# FDC1004Q.net
KiCad netlist of a schematic drawn in EAGLE
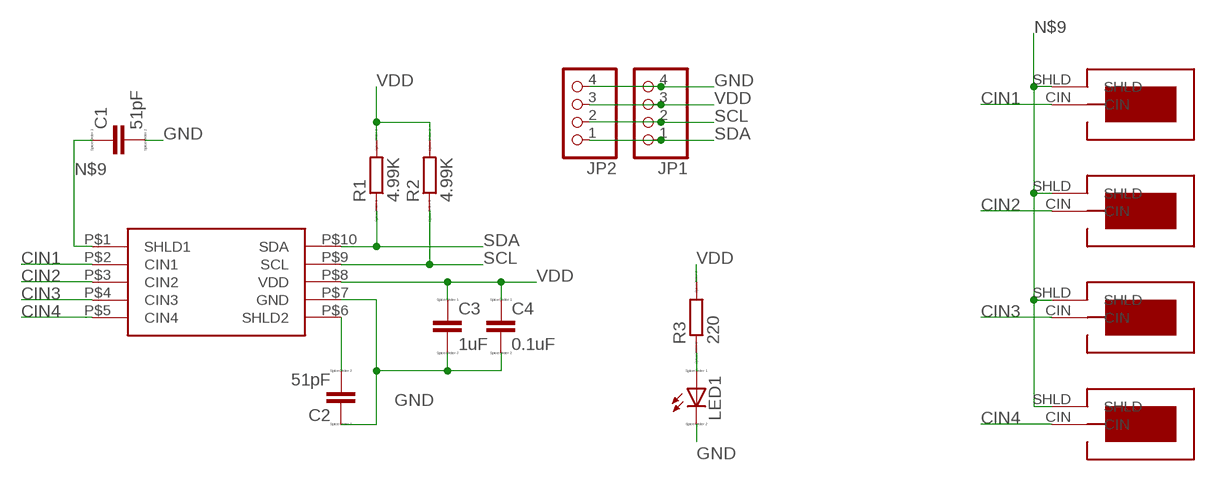
[diagram p0: schematic, sheet 1]

(export (version "E")
  (design (tool "Eeschema 10.0.6"))
  (components
    (comp (ref "C1")
      (value "51pF")
      (footprint "eagle-import:C0805")
      (libsource (lib "eagle-import") (part "C"))
    )
    (comp (ref "C2")
      (value "51pF")
      (footprint "eagle-import:C0805")
      (libsource (lib "eagle-import") (part "C"))
    )
    (comp (ref "C3")
      (value "1uF")
      (footprint "eagle-import:C0805")
      (libsource (lib "eagle-import") (part "C"))
    )
    (comp (ref "C4")
      (value "0.1uF")
      (footprint "eagle-import:C0805")
      (libsource (lib "eagle-import") (part "C"))
    )
    (comp (ref "JP1")
      (value "PINHD-1X4")
      (footprint "eagle-import:1X04")
      (libsource (lib "eagle-import") (part "PINHD-1X4"))
    )
    (comp (ref "JP2")
      (value "PINHD-1X4")
      (footprint "eagle-import:1X04")
      (libsource (lib "eagle-import") (part "PINHD-1X4"))
    )
    (comp (ref "LED1")
      (value "LED_ESML0603")
      (footprint "eagle-import:LED_SML0603")
      (libsource (lib "eagle-import") (part "LED_ESML0603"))
    )
    (comp (ref "R1")
      (value "4.99K")
      (footprint "eagle-import:R0805")
      (libsource (lib "eagle-import") (part "R"))
    )
    (comp (ref "R2")
      (value "4.99K")
      (footprint "eagle-import:R0805")
      (libsource (lib "eagle-import") (part "R"))
    )
    (comp (ref "R3")
      (value "220")
      (footprint "eagle-import:R0805")
      (libsource (lib "eagle-import") (part "R"))
    )
    (comp (ref "SENSOR1")
      (value "SENSOR")
      (footprint "eagle-import:SENSOR_1X1")
      (libsource (lib "eagle-import") (part "SENSOR"))
    )
    (comp (ref "SENSOR2")
      (value "SENSOR")
      (footprint "eagle-import:SENSOR_1X1")
      (libsource (lib "eagle-import") (part "SENSOR"))
    )
    (comp (ref "SENSOR3")
      (value "SENSOR")
      (footprint "eagle-import:SENSOR_1X1")
      (libsource (lib "eagle-import") (part "SENSOR"))
    )
    (comp (ref "SENSOR4")
      (value "SENSOR")
      (footprint "eagle-import:SENSOR_1X1")
      (libsource (lib "eagle-import") (part "SENSOR"))
    )
    (comp (ref "U$1")
      (value "FDC1004Q")
      (footprint "eagle-import:DGS")
      (libsource (lib "eagle-import") (part "FDC1004Q"))
    )
  )
  (nets
    (net (code "1") (name "/CIN1") (class "Default")
      (node (ref "SENSOR1") (pin "CIN") (pinfunction "CIN_CIN") (pintype "bidirectional"))
      (node (ref "U$1") (pin "P$2") (pinfunction "CIN1_P$2") (pintype "bidirectional"))
    )
    (net (code "2") (name "/CIN2") (class "Default")
      (node (ref "SENSOR2") (pin "CIN") (pinfunction "CIN_CIN") (pintype "bidirectional"))
      (node (ref "U$1") (pin "P$3") (pinfunction "CIN2_P$3") (pintype "bidirectional"))
    )
    (net (code "3") (name "/CIN3") (class "Default")
      (node (ref "SENSOR3") (pin "CIN") (pinfunction "CIN_CIN") (pintype "bidirectional"))
      (node (ref "U$1") (pin "P$4") (pinfunction "CIN3_P$4") (pintype "bidirectional"))
    )
    (net (code "4") (name "/CIN4") (class "Default")
      (node (ref "SENSOR4") (pin "CIN") (pinfunction "CIN_CIN") (pintype "bidirectional"))
      (node (ref "U$1") (pin "P$5") (pinfunction "CIN4_P$5") (pintype "bidirectional"))
    )
    (net (code "5") (name "/GND") (class "Default")
      (node (ref "C1") (pin "2") (pinfunction "2_2") (pintype "passive"))
      (node (ref "C2") (pin "1") (pinfunction "1_1") (pintype "passive"))
      (node (ref "C3") (pin "2") (pinfunction "2_2") (pintype "passive"))
      (node (ref "C4") (pin "2") (pinfunction "2_2") (pintype "passive"))
      (node (ref "JP1") (pin "4") (pinfunction "4_4") (pintype "passive"))
      (node (ref "JP2") (pin "4") (pinfunction "4_4") (pintype "passive"))
      (node (ref "LED1") (pin "C") (pinfunction "C_C") (pintype "passive"))
      (node (ref "U$1") (pin "P$7") (pinfunction "GND_P$7") (pintype "bidirectional"))
    )
    (net (code "6") (name "/N$9") (class "Default")
      (node (ref "C1") (pin "1") (pinfunction "1_1") (pintype "passive"))
      (node (ref "SENSOR1") (pin "SHLD") (pinfunction "SHLD_SHLD") (pintype "bidirectional"))
      (node (ref "SENSOR2") (pin "SHLD") (pinfunction "SHLD_SHLD") (pintype "bidirectional"))
      (node (ref "SENSOR3") (pin "SHLD") (pinfunction "SHLD_SHLD") (pintype "bidirectional"))
      (node (ref "SENSOR4") (pin "SHLD") (pinfunction "SHLD_SHLD") (pintype "bidirectional"))
      (node (ref "U$1") (pin "P$1") (pinfunction "SHLD1_P$1") (pintype "bidirectional"))
    )
    (net (code "7") (name "/SCL") (class "Default")
      (node (ref "JP1") (pin "2") (pinfunction "2_2") (pintype "passive"))
      (node (ref "JP2") (pin "2") (pinfunction "2_2") (pintype "passive"))
      (node (ref "R2") (pin "1") (pinfunction "1_1") (pintype "passive"))
      (node (ref "U$1") (pin "P$9") (pinfunction "SCL_P$9") (pintype "bidirectional"))
    )
    (net (code "8") (name "/SDA") (class "Default")
      (node (ref "JP1") (pin "1") (pinfunction "1_1") (pintype "passive"))
      (node (ref "JP2") (pin "1") (pinfunction "1_1") (pintype "passive"))
      (node (ref "R1") (pin "1") (pinfunction "1_1") (pintype "passive"))
      (node (ref "U$1") (pin "P$10") (pinfunction "SDA_P$10") (pintype "bidirectional"))
    )
    (net (code "9") (name "/VDD") (class "Default")
      (node (ref "C3") (pin "1") (pinfunction "1_1") (pintype "passive"))
      (node (ref "C4") (pin "1") (pinfunction "1_1") (pintype "passive"))
      (node (ref "JP1") (pin "3") (pinfunction "3_3") (pintype "passive"))
      (node (ref "JP2") (pin "3") (pinfunction "3_3") (pintype "passive"))
      (node (ref "R1") (pin "2") (pinfunction "2_2") (pintype "passive"))
      (node (ref "R2") (pin "2") (pinfunction "2_2") (pintype "passive"))
      (node (ref "R3") (pin "2") (pinfunction "2_2") (pintype "passive"))
      (node (ref "U$1") (pin "P$8") (pinfunction "VDD_P$8") (pintype "bidirectional"))
    )
    (net (code "10") (name "Net-(LED1-PadA)") (class "Default")
      (node (ref "LED1") (pin "A") (pinfunction "A_A") (pintype "passive"))
      (node (ref "R3") (pin "1") (pinfunction "1_1") (pintype "passive"))
    )
    (net (code "11") (name "Net-(U$1-SHLD2)") (class "Default")
      (node (ref "C2") (pin "2") (pinfunction "2_2") (pintype "passive"))
      (node (ref "U$1") (pin "P$6") (pinfunction "SHLD2_P$6") (pintype "bidirectional"))
    )
  )
)
